# ext_supply.net
KiCad netlist of a schematic drawn in Altium Designer
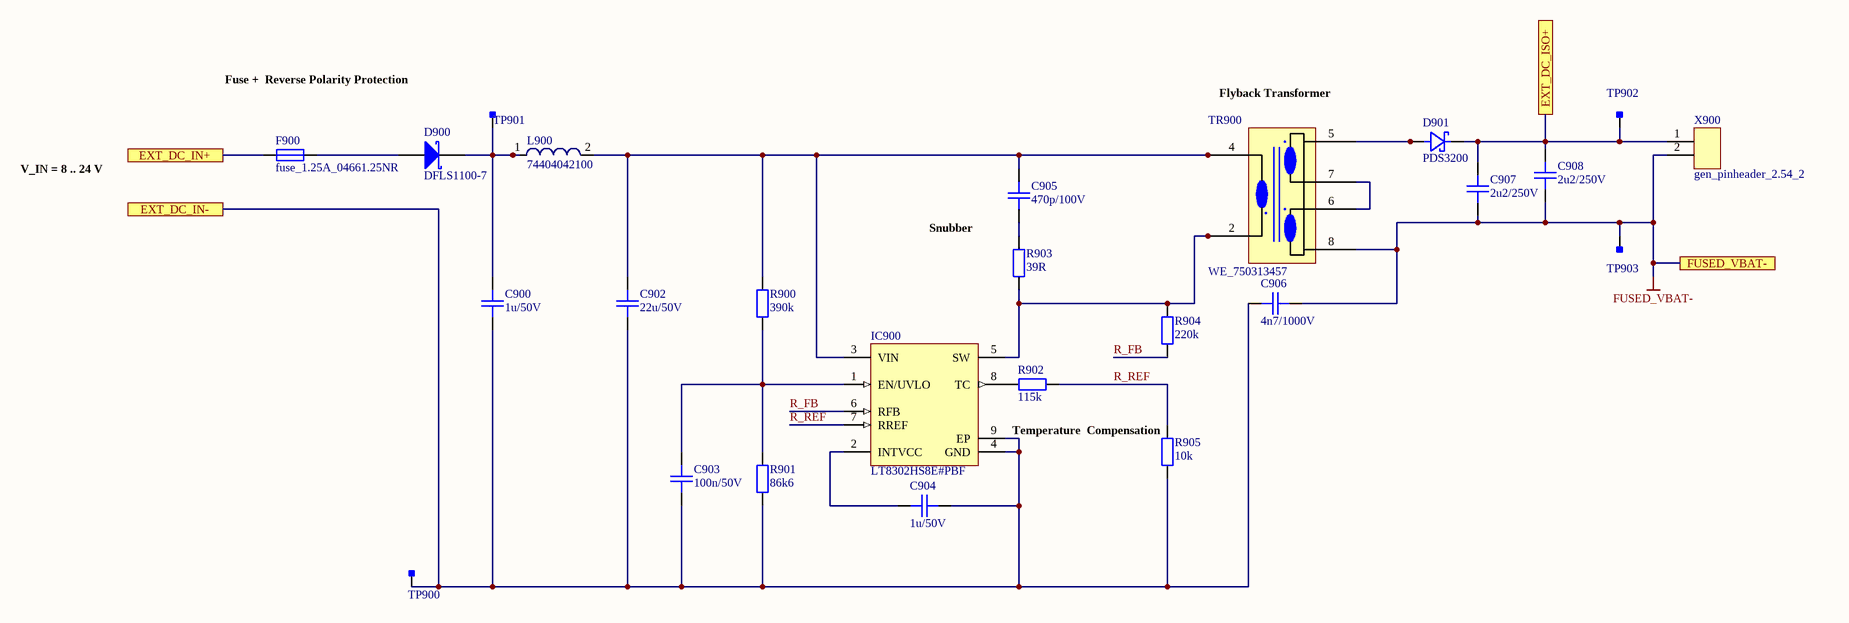
[diagram p0: ext_supply.SchDoc]

(export (version "E")
  (design (tool "Eeschema 10.0.6"))
  (components
    (comp (ref "C900")
      (value "1u/50V")
      (footprint "CAPC2012X14N")
      (description "MLCC")
      (fields (field (name "PART NUMBER") "gen_C_ceramic_1u_50V_X7R_0805") (field (name "TOLERANCE") "± 10%"))
      (libsource (lib "OE750") (part "C"))
    )
    (comp (ref "C902")
      (value "22u/50V")
      (footprint "CAPC2220(5750)230_N")
      (description "MLCC")
      (fields (field (name "PART NUMBER") "gen_C_ceramic_22u_50V_X7R_2220_stacked"))
      (libsource (lib "OE750") (part "C"))
    )
    (comp (ref "C903")
      (value "100n/50V")
      (footprint "CAPC1608X08N")
      (description "MLCC")
      (fields (field (name "PART NUMBER") "gen_C_ceramic_100n_50V_X7R_0603"))
      (libsource (lib "OE750") (part "C"))
    )
    (comp (ref "C904")
      (value "1u/50V")
      (footprint "CAPC2012X14N")
      (description "MLCC")
      (fields (field (name "PART NUMBER") "gen_C_ceramic_1u_50V_X7R_0805") (field (name "TOLERANCE") "± 10%"))
      (libsource (lib "OE750") (part "C"))
    )
    (comp (ref "C905")
      (value "470p/100V")
      (footprint "CAPC2012X14N")
      (description "MLCC")
      (fields (field (name "PART NUMBER") "gen_C_ceramic_470p_100V_X7R_0805"))
      (libsource (lib "OE750") (part "C"))
    )
    (comp (ref "C906")
      (value "4n7/1000V")
      (footprint "CAPC4532X16N")
      (description "MLCC")
      (fields (field (name "PART NUMBER") "gen_C_ceramic_4n7_1000V_X7R_1812"))
      (libsource (lib "OE750") (part "C"))
    )
    (comp (ref "C907")
      (value "2u2/250V")
      (footprint "CAPC2220(5750)230_N")
      (description "MLCC")
      (fields (field (name "PART NUMBER") "gen_C_ceramic_2u2_250V_X7R_2220"))
      (libsource (lib "OE750") (part "C"))
    )
    (comp (ref "C908")
      (value "2u2/250V")
      (footprint "CAPC2220(5750)230_N")
      (description "MLCC")
      (fields (field (name "PART NUMBER") "gen_C_ceramic_2u2_250V_X7R_2220"))
      (libsource (lib "OE750") (part "C"))
    )
    (comp (ref "D900")
      (value "DFLS1100-7")
      (footprint "DIOD-POWERDI123-2_V")
      (fields (field (name "MANUFACTURER") "Diodes Inc"))
      (libsource (lib "Altium Content Vault") (part "DSKY-AK-2"))
    )
    (comp (ref "D901")
      (value "PDS3200")
      (footprint "PowerDI5")
      (description "Schottky Diode 3A 200V 780mV")
      (fields (field (name "PART NUMBER") "PDS3200-13") (field (name "MANUFACTURER") "DIODES Inc"))
      (libsource (lib "OE750") (part "PDS3200"))
    )
    (comp (ref "F900")
      (value "fuse_1.25A_04661.25NR")
      (footprint "LITTLEFUSE_466")
      (description "Fuse, Surface Mount, 466 Series, 1.25 A, 63 VAC, 63 VDC, Very Fast Acting, 1206")
      (fields (field (name "MANUFACTURER") "Littlefuse"))
      (libsource (lib "OE750") (part "R_Fuse"))
    )
    (comp (ref "IC900")
      (value "LT8302HS8E#PBF")
      (footprint "LT-S8E-8_V")
      (fields (field (name "PARTNUMBER") "LT8302"))
      (libsource (lib "Altium Content Vault") (part "LT-LT8302-S8E-8"))
    )
    (comp (ref "L900")
      (value "74404042100")
      (footprint "WE-LQS 4018")
      (description "WE-LQS SMD Power Inductor, L=10 µH")
      (fields (field (name "MANUFACTURER") "Wuerth Elektronik"))
      (libsource (lib "Altium Content Vault") (part "WE-IND-INDUCTOR-2"))
    )
    (comp (ref "R900")
      (value "390k")
      (footprint "RESC1608X05N")
      (description "SMD Resistor 390k 0603")
      (fields (field (name "PART NUMBER") "gen_R_390k_0603") (field (name "TOLERANCE") "1%"))
      (libsource (lib "OE750") (part "R"))
    )
    (comp (ref "R901")
      (value "86k6")
      (footprint "RESC1608X05N")
      (description "SMD Resistor 86k6 0603")
      (fields (field (name "PART NUMBER") "gen_R_86k6_0603") (field (name "TOLERANCE") "1%"))
      (libsource (lib "OE750") (part "R"))
    )
    (comp (ref "R902")
      (value "115k")
      (footprint "RESC1608X05N")
      (description "SMD Resistor 115k 0603")
      (fields (field (name "PART NUMBER") "gen_R_115k_0603") (field (name "TOLERANCE") "1%"))
      (libsource (lib "OE750") (part "R"))
    )
    (comp (ref "R903")
      (value "39R")
      (footprint "RESC2012X05N")
      (description "SMD Resistor 39R 0805")
      (fields (field (name "PART NUMBER") "gen_R_39R_0805") (field (name "TOLERANCE") "1%"))
      (libsource (lib "OE750") (part "R"))
    )
    (comp (ref "R904")
      (value "220k")
      (footprint "RESC1608X05N")
      (description "SMD Resistor 220k 0603")
      (fields (field (name "PART NUMBER") "gen_R_220k_0603") (field (name "TOLERANCE") "1%"))
      (libsource (lib "OE750") (part "R"))
    )
    (comp (ref "R905")
      (value "10k")
      (footprint "RESC1608X05N")
      (description "SMD Resistor 10k 0603")
      (fields (field (name "PART NUMBER") "gen_R_10k_0603") (field (name "TOLERANCE") "1%"))
      (libsource (lib "OE750") (part "R"))
    )
    (comp (ref "TP900")
      (value "Testpoint_Square")
      (footprint "Testpoint_S1")
      (description "Testpoint, square")
      (libsource (lib "OE750") (part "Testpoint_Square"))
    )
    (comp (ref "TP901")
      (value "Testpoint_Square")
      (footprint "Testpoint_S1")
      (description "Testpoint, square")
      (libsource (lib "OE750") (part "Testpoint_Square"))
    )
    (comp (ref "TP902")
      (value "Testpoint_Square")
      (footprint "Testpoint_S1")
      (description "Testpoint, square")
      (libsource (lib "OE750") (part "Testpoint_Square"))
    )
    (comp (ref "TP903")
      (value "Testpoint_Square")
      (footprint "Testpoint_S1")
      (description "Testpoint, square")
      (libsource (lib "OE750") (part "Testpoint_Square"))
    )
    (comp (ref "TR900")
      (value "WE_750313457")
      (footprint "WE_750313457")
      (description "MID-FLYLT Flyback Transformers for Linear Technology")
      (fields (field (name "MANUFACTURER") "Würth Elektronik"))
      (libsource (lib "OE750") (part "WE_750313457"))
    )
    (comp (ref "X900")
      (value "gen_pinheader_2.54_2")
      (footprint "Pinheader_2.54_2")
      (description "Standard Pinheader, THD, gerade, 2.54mm")
      (libsource (lib "OE750") (part "X2"))
    )
  )
  (nets
    (net (code "1") (name "/EXT_DC_IN+") (class "Default")
      (node (ref "F900") (pin "1") (pinfunction "1_1") (pintype "passive"))
    )
    (net (code "2") (name "/EXT_DC_IN-") (class "Default")
      (node (ref "C900") (pin "1") (pinfunction "1_1") (pintype "passive"))
      (node (ref "C902") (pin "1") (pinfunction "1_1") (pintype "passive"))
      (node (ref "C903") (pin "1") (pinfunction "1_1") (pintype "passive"))
      (node (ref "C904") (pin "1") (pinfunction "1_1") (pintype "passive"))
      (node (ref "C906") (pin "1") (pinfunction "1_1") (pintype "passive"))
      (node (ref "IC900") (pin "4") (pinfunction "GND_4") (pintype "power_in"))
      (node (ref "IC900") (pin "9") (pinfunction "EP_9") (pintype "power_in"))
      (node (ref "R901") (pin "1") (pinfunction "1_1") (pintype "passive"))
      (node (ref "R905") (pin "1") (pinfunction "1_1") (pintype "passive"))
      (node (ref "TP900") (pin "1") (pinfunction "1_1") (pintype "passive"))
    )
    (net (code "3") (name "/EXT_DC_ISO+") (class "Default")
      (node (ref "C907") (pin "2") (pinfunction "2_2") (pintype "passive"))
      (node (ref "C908") (pin "2") (pinfunction "2_2") (pintype "passive"))
      (node (ref "D901") (pin "1") (pinfunction "C_1") (pintype "passive"))
      (node (ref "TP902") (pin "1") (pinfunction "1_1") (pintype "passive"))
      (node (ref "X900") (pin "1") (pintype "passive"))
    )
    (net (code "4") (name "/R_FB") (class "Default")
      (node (ref "IC900") (pin "6") (pinfunction "RFB_6") (pintype "input"))
      (node (ref "R904") (pin "1") (pinfunction "1_1") (pintype "passive"))
    )
    (net (code "5") (name "/R_REF") (class "Default")
      (node (ref "IC900") (pin "7") (pinfunction "RREF_7") (pintype "input"))
      (node (ref "R902") (pin "2") (pinfunction "2_2") (pintype "passive"))
      (node (ref "R905") (pin "2") (pinfunction "2_2") (pintype "passive"))
    )
    (net (code "6") (name "FUSED_VBAT-") (class "Default")
      (node (ref "C906") (pin "2") (pinfunction "2_2") (pintype "passive"))
      (node (ref "C907") (pin "1") (pinfunction "1_1") (pintype "passive"))
      (node (ref "C908") (pin "1") (pinfunction "1_1") (pintype "passive"))
      (node (ref "TP903") (pin "1") (pinfunction "1_1") (pintype "passive"))
      (node (ref "TR900") (pin "8") (pinfunction "8_8") (pintype "passive"))
      (node (ref "X900") (pin "2") (pintype "passive"))
    )
    (net (code "7") (name "Net-(C905-Pad1)") (class "Default")
      (node (ref "C905") (pin "1") (pinfunction "1_1") (pintype "passive"))
      (node (ref "R903") (pin "2") (pinfunction "2_2") (pintype "passive"))
    )
    (net (code "8") (name "Net-(D900-A)") (class "Default")
      (node (ref "D900") (pin "1") (pinfunction "A_1") (pintype "passive"))
      (node (ref "F900") (pin "2") (pinfunction "2_2") (pintype "passive"))
    )
    (net (code "9") (name "Net-(D900-K)") (class "Default")
      (node (ref "C900") (pin "2") (pinfunction "2_2") (pintype "passive"))
      (node (ref "D900") (pin "2") (pinfunction "K_2") (pintype "passive"))
      (node (ref "L900") (pin "1") (pinfunction "1_1") (pintype "passive"))
      (node (ref "TP901") (pin "1") (pinfunction "1_1") (pintype "passive"))
    )
    (net (code "10") (name "Net-(D901-A-Pad2)") (class "Default")
      (node (ref "D901") (pin "2") (pinfunction "A_2") (pintype "passive"))
      (node (ref "D901") (pin "3") (pinfunction "A_3") (pintype "passive"))
      (node (ref "TR900") (pin "5") (pinfunction "5_5") (pintype "passive"))
    )
    (net (code "11") (name "Net-(IC900-EN{slash}UVLO)") (class "Default")
      (node (ref "C903") (pin "2") (pinfunction "2_2") (pintype "passive"))
      (node (ref "IC900") (pin "1") (pinfunction "EN/UVLO_1") (pintype "input"))
      (node (ref "R900") (pin "1") (pinfunction "1_1") (pintype "passive"))
      (node (ref "R901") (pin "2") (pinfunction "2_2") (pintype "passive"))
    )
    (net (code "12") (name "Net-(IC900-INTVCC)") (class "Default")
      (node (ref "C904") (pin "2") (pinfunction "2_2") (pintype "passive"))
      (node (ref "IC900") (pin "2") (pinfunction "INTVCC_2") (pintype "power_in"))
    )
    (net (code "13") (name "Net-(IC900-SW)") (class "Default")
      (node (ref "IC900") (pin "5") (pinfunction "SW_5") (pintype "power_in"))
      (node (ref "R903") (pin "1") (pinfunction "1_1") (pintype "passive"))
      (node (ref "R904") (pin "2") (pinfunction "2_2") (pintype "passive"))
      (node (ref "TR900") (pin "1") (pinfunction "1_1") (pintype "passive"))
      (node (ref "TR900") (pin "2") (pinfunction "2_2") (pintype "passive"))
    )
    (net (code "14") (name "Net-(IC900-TC)") (class "Default")
      (node (ref "IC900") (pin "8") (pinfunction "TC_8") (pintype "output"))
      (node (ref "R902") (pin "1") (pinfunction "1_1") (pintype "passive"))
    )
    (net (code "15") (name "Net-(IC900-VIN)") (class "Default")
      (node (ref "C902") (pin "2") (pinfunction "2_2") (pintype "passive"))
      (node (ref "C905") (pin "2") (pinfunction "2_2") (pintype "passive"))
      (node (ref "IC900") (pin "3") (pinfunction "VIN_3") (pintype "power_in"))
      (node (ref "L900") (pin "2") (pinfunction "2_2") (pintype "passive"))
      (node (ref "R900") (pin "2") (pinfunction "2_2") (pintype "passive"))
      (node (ref "TR900") (pin "3") (pinfunction "3_3") (pintype "passive"))
      (node (ref "TR900") (pin "4") (pinfunction "4_4") (pintype "passive"))
    )
    (net (code "16") (name "Net-(TR900-Pad6)") (class "Default")
      (node (ref "TR900") (pin "6") (pinfunction "6_6") (pintype "passive"))
      (node (ref "TR900") (pin "7") (pinfunction "7_7") (pintype "passive"))
    )
  )
)
